# working.net
KiCad netlist of a schematic drawn in EAGLE
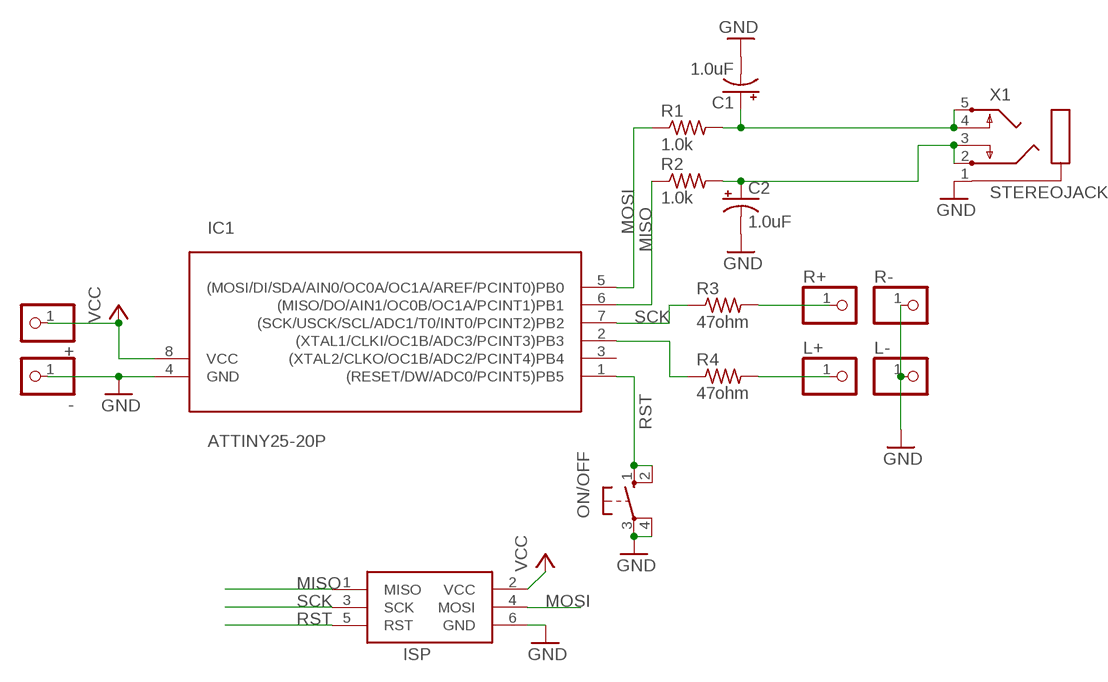
[diagram p0: schematic, sheet 1]

(export (version "E")
  (design (tool "Eeschema 10.0.6"))
  (components
    (comp (ref "+")
      (value "PINHD-1X1")
      (footprint "eagle-import:1X01")
      (libsource (lib "eagle-import") (part "PINHD-1X1"))
    )
    (comp (ref "-")
      (value "PINHD-1X1")
      (footprint "eagle-import:1X01")
      (libsource (lib "eagle-import") (part "PINHD-1X1"))
    )
    (comp (ref "C1")
      (value "1.0uF")
      (footprint "eagle-import:E2,5-5")
      (libsource (lib "eagle-import") (part "CPOL-USE2.5-5"))
    )
    (comp (ref "C2")
      (value "1.0uF")
      (footprint "eagle-import:E2,5-5")
      (libsource (lib "eagle-import") (part "CPOL-USE2.5-5"))
    )
    (comp (ref "IC1")
      (value "ATTINY25-20P")
      (footprint "eagle-import:DIL08")
      (libsource (lib "eagle-import") (part "ATTINY25P-20"))
    )
    (comp (ref "ISP")
      (value "AVRISP-6")
      (footprint "eagle-import:AVRISP")
      (libsource (lib "eagle-import") (part "AVRISP-6"))
    )
    (comp (ref "L+")
      (value "PINHD-1X1")
      (footprint "eagle-import:1X01")
      (libsource (lib "eagle-import") (part "PINHD-1X1"))
    )
    (comp (ref "L-")
      (value "PINHD-1X1")
      (footprint "eagle-import:1X01")
      (libsource (lib "eagle-import") (part "PINHD-1X1"))
    )
    (comp (ref "ON/OFF")
      (value "10-XX")
      (footprint "eagle-import:B3F-10XX")
      (libsource (lib "eagle-import") (part "10-XX"))
    )
    (comp (ref "R+")
      (value "PINHD-1X1")
      (footprint "eagle-import:1X01")
      (libsource (lib "eagle-import") (part "PINHD-1X1"))
    )
    (comp (ref "R-")
      (value "PINHD-1X1")
      (footprint "eagle-import:1X01")
      (libsource (lib "eagle-import") (part "PINHD-1X1"))
    )
    (comp (ref "R1")
      (value "1.0k")
      (footprint "eagle-import:0207_10")
      (libsource (lib "eagle-import") (part "R-US_0207/10"))
    )
    (comp (ref "R2")
      (value "1.0k")
      (footprint "eagle-import:0207_10")
      (libsource (lib "eagle-import") (part "R-US_0207/10"))
    )
    (comp (ref "R3")
      (value "47ohm")
      (footprint "eagle-import:0207_10")
      (libsource (lib "eagle-import") (part "R-US_0207/10"))
    )
    (comp (ref "R4")
      (value "47ohm")
      (footprint "eagle-import:0207_10")
      (libsource (lib "eagle-import") (part "R-US_0207/10"))
    )
    (comp (ref "X1")
      (value "STEREOJACK")
      (footprint "eagle-import:STX3100")
      (libsource (lib "eagle-import") (part "STEREOJACK"))
    )
  )
  (nets
    (net (code "1") (name "/MISO") (class "Default")
      (node (ref "IC1") (pin "6") (pinfunction "(MISO/DO/AIN1/OC0B/OC1A/PCINT1)PB1_6") (pintype "bidirectional"))
      (node (ref "ISP") (pin "1") (pinfunction "MISO_1") (pintype "input"))
      (node (ref "R2") (pin "1") (pinfunction "1_1") (pintype "passive"))
    )
    (net (code "2") (name "/MOSI") (class "Default")
      (node (ref "IC1") (pin "5") (pinfunction "(MOSI/DI/SDA/AIN0/OC0A/OC1A/AREF/PCINT0)PB0_5") (pintype "bidirectional"))
      (node (ref "ISP") (pin "4") (pinfunction "MOSI_4") (pintype "output"))
      (node (ref "R1") (pin "1") (pinfunction "1_1") (pintype "passive"))
    )
    (net (code "3") (name "/RST") (class "Default")
      (node (ref "IC1") (pin "1") (pinfunction "(RESET/DW/ADC0/PCINT5)PB5_1") (pintype "bidirectional"))
      (node (ref "ISP") (pin "5") (pinfunction "RST_5") (pintype "output"))
      (node (ref "ON/OFF") (pin "1") (pinfunction "S_1") (pintype "passive"))
      (node (ref "ON/OFF") (pin "2") (pinfunction "S1_2") (pintype "passive"))
    )
    (net (code "4") (name "/SCK") (class "Default")
      (node (ref "IC1") (pin "7") (pinfunction "(SCK/USCK/SCL/ADC1/T0/INT0/PCINT2)PB2_7") (pintype "bidirectional"))
      (node (ref "ISP") (pin "3") (pinfunction "SCK_3") (pintype "output"))
      (node (ref "R3") (pin "1") (pinfunction "1_1") (pintype "passive"))
    )
    (net (code "5") (name "GND") (class "Default")
      (node (ref "-") (pin "1") (pinfunction "1_1") (pintype "passive"))
      (node (ref "C1") (pin "-") (pinfunction "-_-") (pintype "passive"))
      (node (ref "C2") (pin "-") (pinfunction "-_-") (pintype "passive"))
      (node (ref "IC1") (pin "4") (pinfunction "GND_4") (pintype "bidirectional"))
      (node (ref "ISP") (pin "6") (pinfunction "GND_6") (pintype "power_in"))
      (node (ref "L-") (pin "1") (pinfunction "1_1") (pintype "passive"))
      (node (ref "ON/OFF") (pin "3") (pinfunction "P_3") (pintype "passive"))
      (node (ref "ON/OFF") (pin "4") (pinfunction "P1_4") (pintype "passive"))
      (node (ref "R-") (pin "1") (pinfunction "1_1") (pintype "passive"))
      (node (ref "X1") (pin "1") (pinfunction "1_1") (pintype "passive"))
    )
    (net (code "6") (name "Net-(C1-Pad+)") (class "Default")
      (node (ref "C1") (pin "+") (pinfunction "+_+") (pintype "passive"))
      (node (ref "R1") (pin "2") (pinfunction "2_2") (pintype "passive"))
      (node (ref "X1") (pin "4") (pinfunction "4_4") (pintype "passive"))
      (node (ref "X1") (pin "5") (pinfunction "5_5") (pintype "passive"))
    )
    (net (code "7") (name "Net-(C2-Pad+)") (class "Default")
      (node (ref "C2") (pin "+") (pinfunction "+_+") (pintype "passive"))
      (node (ref "R2") (pin "2") (pinfunction "2_2") (pintype "passive"))
      (node (ref "X1") (pin "2") (pinfunction "2_2") (pintype "passive"))
      (node (ref "X1") (pin "3") (pinfunction "3_3") (pintype "passive"))
    )
    (net (code "8") (name "Net-(IC1-(XTAL1{slash}CLKI{slash}OC1B{slash}ADC3{slash}PCINT3)PB3)") (class "Default")
      (node (ref "IC1") (pin "2") (pinfunction "(XTAL1/CLKI/OC1B/ADC3/PCINT3)PB3_2") (pintype "bidirectional"))
      (node (ref "R4") (pin "1") (pinfunction "1_1") (pintype "passive"))
    )
    (net (code "9") (name "Net-(L+-Pad1)") (class "Default")
      (node (ref "L+") (pin "1") (pinfunction "1_1") (pintype "passive"))
      (node (ref "R4") (pin "2") (pinfunction "2_2") (pintype "passive"))
    )
    (net (code "10") (name "Net-(R+-Pad1)") (class "Default")
      (node (ref "R+") (pin "1") (pinfunction "1_1") (pintype "passive"))
      (node (ref "R3") (pin "2") (pinfunction "2_2") (pintype "passive"))
    )
    (net (code "11") (name "VCC") (class "Default")
      (node (ref "+") (pin "1") (pinfunction "1_1") (pintype "passive"))
      (node (ref "IC1") (pin "8") (pinfunction "VCC_8") (pintype "bidirectional"))
      (node (ref "ISP") (pin "2") (pinfunction "VCC_2") (pintype "power_in"))
    )
    (net (code "12") (name "unconnected-(IC1-(XTAL2{slash}CLKO{slash}OC1B{slash}ADC2{slash}PCINT4)PB4-Pad3)") (class "Default")
      (node (ref "IC1") (pin "3") (pinfunction "(XTAL2/CLKO/OC1B/ADC2/PCINT4)PB4_3") (pintype "bidirectional"))
    )
  )
)
